# ProProject__CW32__2024-01-23.net
KiCad netlist of a schematic drawn in EasyEDA Pro
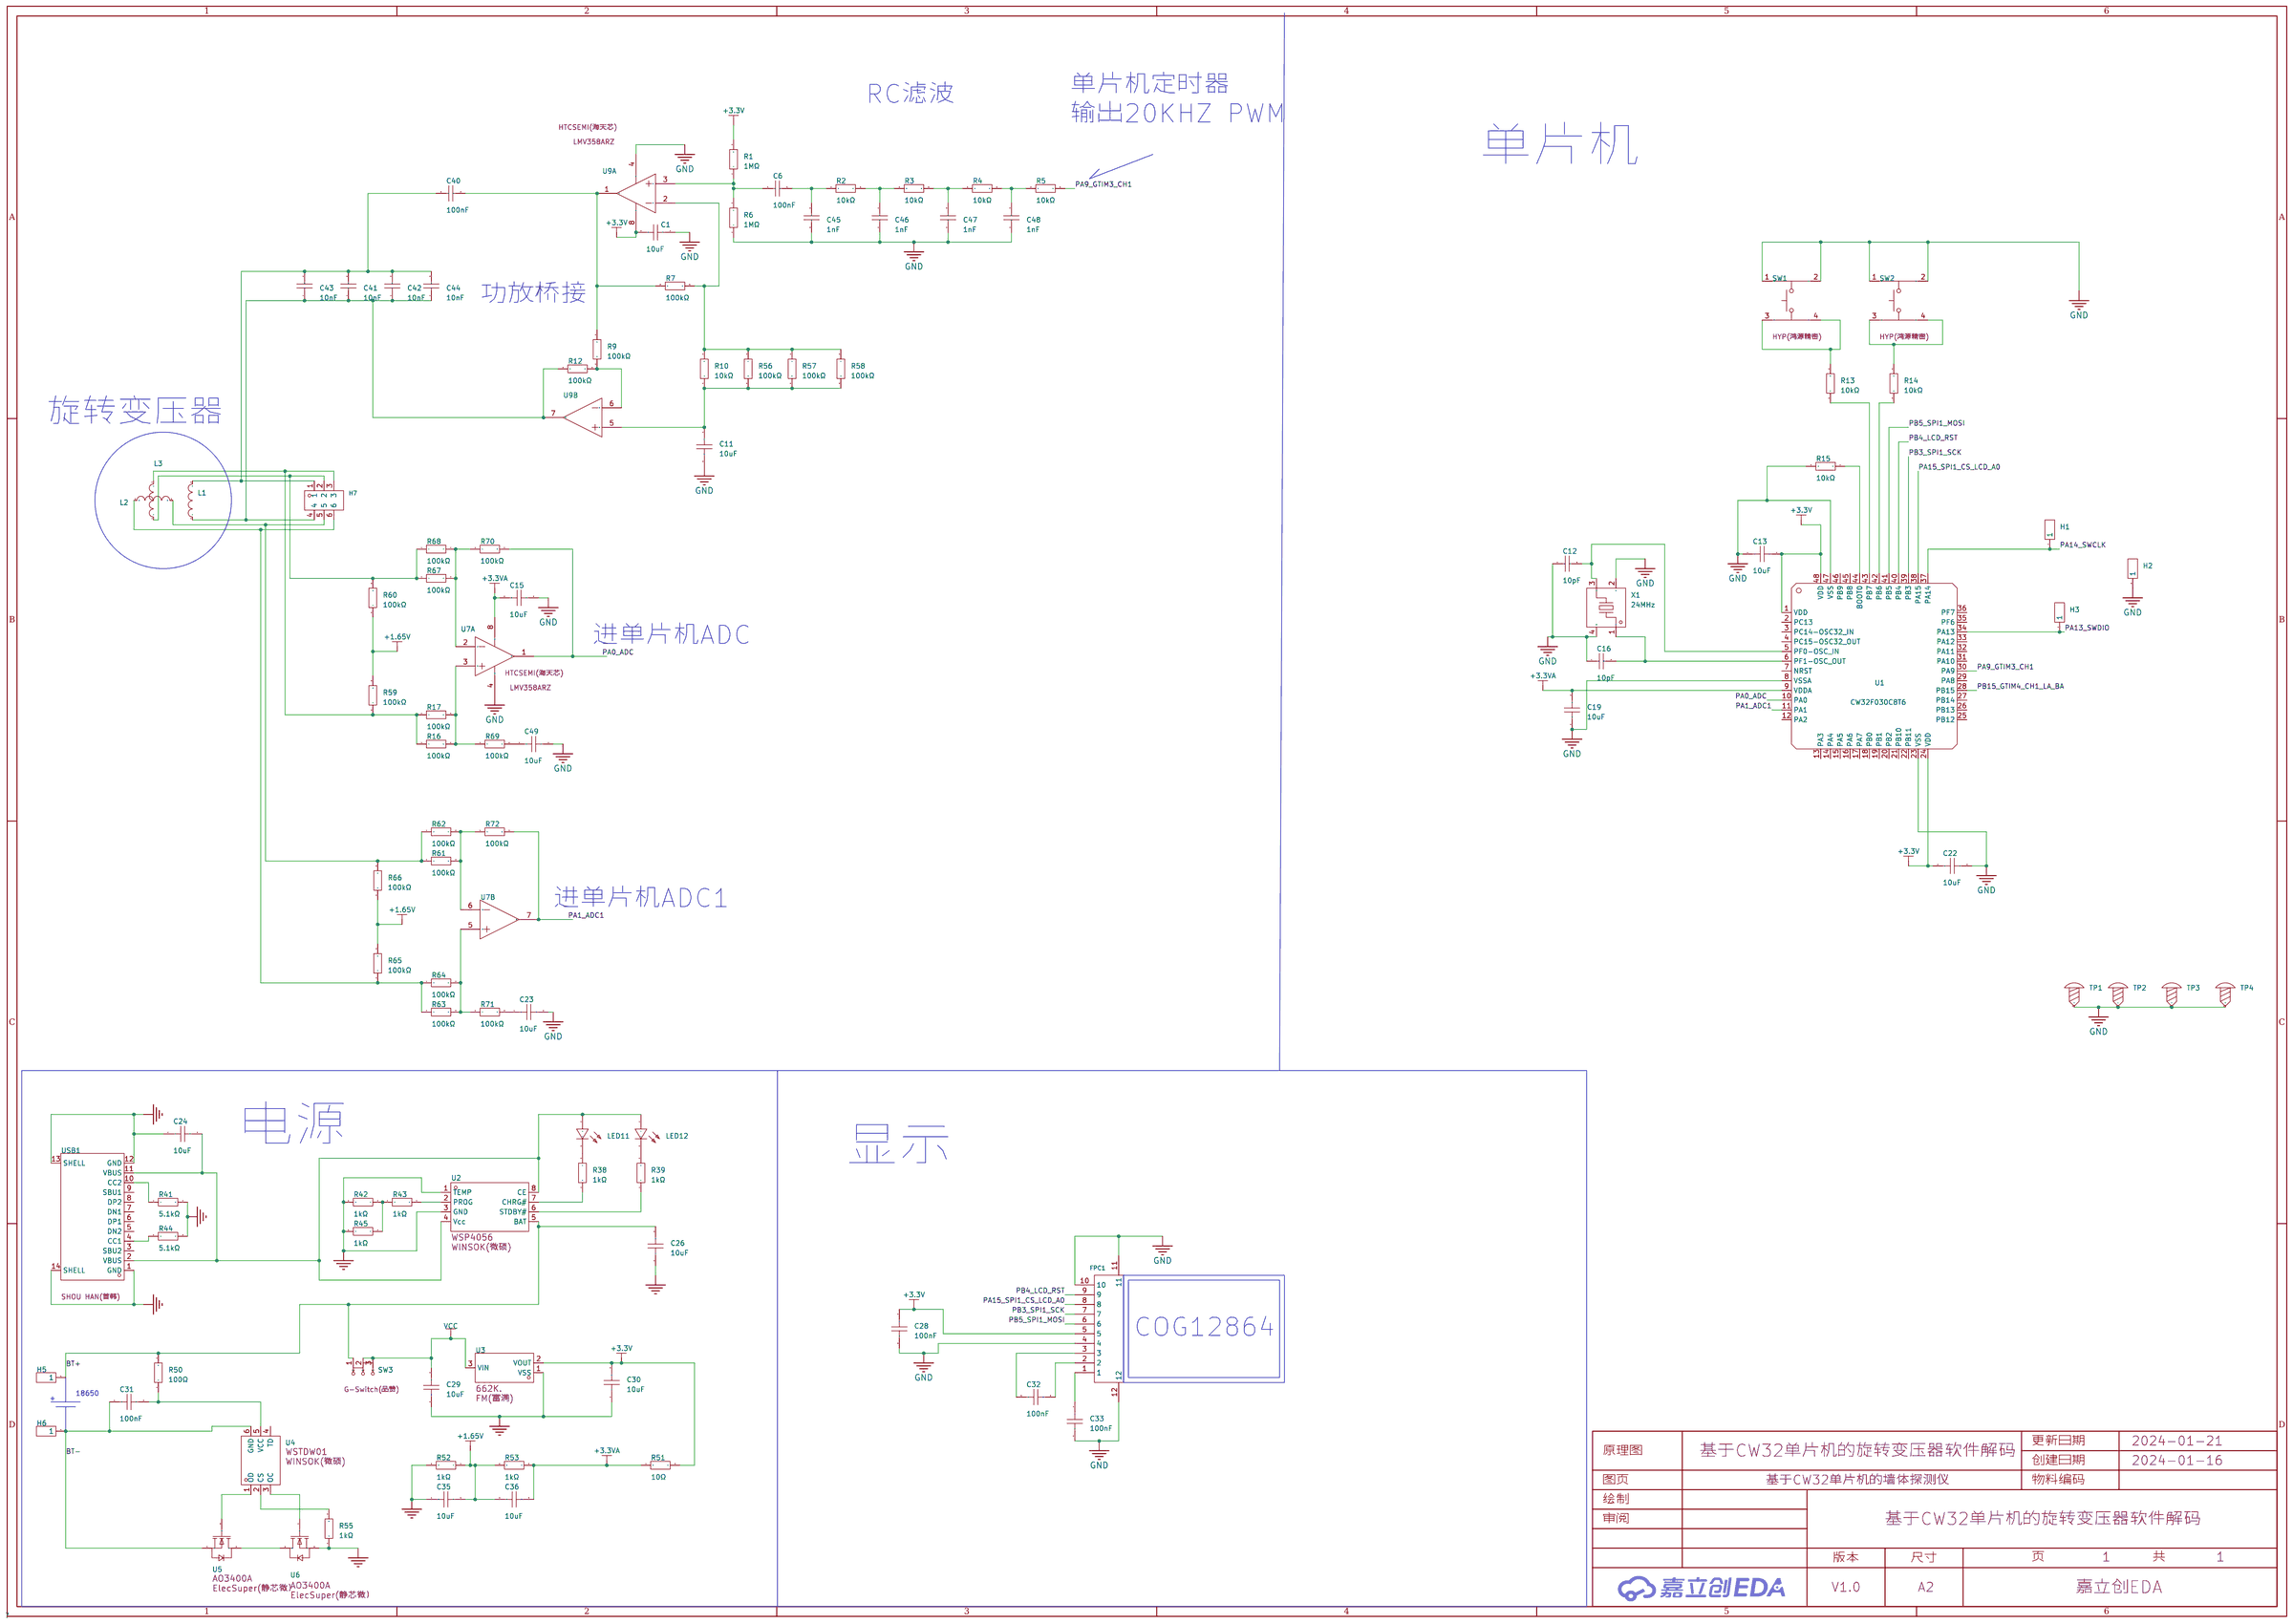
[diagram p0: schematic sheet]

(export (version "E")
  (design (tool "Eeschema 10.0.6"))
  (components
    (comp (ref "C1")
      (value "10uF")
      (footprint "easyedapro:C0603")
      (description "容值:10uF;精度:±10%;额定电压:10V;材质(温度系数):X5R;")
      (fields
        (field (name "Manufacturer Part") "CL10A106KP8NNNC")
        (field (name "Manufacturer") "SAMSUNG(三星)")
      )
      (libsource (lib "easyedapro") (part "CL10A106KP8NNNC"))
    )
    (comp (ref "C6")
      (value "100nF")
      (footprint "easyedapro:C0603")
      (description "容值:100nF;精度:±10%;额定电压:50V;材质(温度系数):X7R;")
      (fields (field (name "Manufacturer Part") "0603B104K500NT") (field (name "Manufacturer") "FH(风华)"))
      (libsource (lib "easyedapro") (part "0603B104K500NT"))
    )
    (comp (ref "C11")
      (value "10uF")
      (footprint "easyedapro:C0603")
      (description "容值:10uF;精度:±10%;额定电压:10V;材质(温度系数):X5R;")
      (fields
        (field (name "Manufacturer Part") "CL10A106KP8NNNC")
        (field (name "Manufacturer") "SAMSUNG(三星)")
      )
      (libsource (lib "easyedapro") (part "CL10A106KP8NNNC"))
    )
    (comp (ref "C12")
      (value "10pF")
      (footprint "easyedapro:C0603")
      (description "容值:10pF;精度:±5%;额定电压:50V;材质(温度系数):NP0;")
      (fields
        (field (name "Manufacturer Part") "CC0603JRNPO9BN100")
        (field (name "Manufacturer") "YAGEO(国巨)")
      )
      (libsource (lib "easyedapro") (part "CC0603JRNPO9BN100"))
    )
    (comp (ref "C13")
      (value "10uF")
      (footprint "easyedapro:C0603")
      (description "容值:10uF;精度:±10%;额定电压:10V;材质(温度系数):X5R;")
      (fields
        (field (name "Manufacturer Part") "CL10A106KP8NNNC")
        (field (name "Manufacturer") "SAMSUNG(三星)")
      )
      (libsource (lib "easyedapro") (part "CL10A106KP8NNNC"))
    )
    (comp (ref "C15")
      (value "10uF")
      (footprint "easyedapro:C0603")
      (description "容值:10uF;精度:±10%;额定电压:10V;材质(温度系数):X5R;")
      (fields
        (field (name "Manufacturer Part") "CL10A106KP8NNNC")
        (field (name "Manufacturer") "SAMSUNG(三星)")
      )
      (libsource (lib "easyedapro") (part "CL10A106KP8NNNC"))
    )
    (comp (ref "C16")
      (value "10pF")
      (footprint "easyedapro:C0603")
      (description "容值:10pF;精度:±5%;额定电压:50V;材质(温度系数):NP0;")
      (fields
        (field (name "Manufacturer Part") "CC0603JRNPO9BN100")
        (field (name "Manufacturer") "YAGEO(国巨)")
      )
      (libsource (lib "easyedapro") (part "CC0603JRNPO9BN100"))
    )
    (comp (ref "C19")
      (value "10uF")
      (footprint "easyedapro:C0603")
      (description "容值:10uF;精度:±10%;额定电压:10V;材质(温度系数):X5R;")
      (fields
        (field (name "Manufacturer Part") "CL10A106KP8NNNC")
        (field (name "Manufacturer") "SAMSUNG(三星)")
      )
      (libsource (lib "easyedapro") (part "CL10A106KP8NNNC"))
    )
    (comp (ref "C22")
      (value "10uF")
      (footprint "easyedapro:C0603")
      (description "容值:10uF;精度:±10%;额定电压:10V;材质(温度系数):X5R;")
      (fields
        (field (name "Manufacturer Part") "CL10A106KP8NNNC")
        (field (name "Manufacturer") "SAMSUNG(三星)")
      )
      (libsource (lib "easyedapro") (part "CL10A106KP8NNNC"))
    )
    (comp (ref "C23")
      (value "10uF")
      (footprint "easyedapro:C0603")
      (description "容值:10uF;精度:±10%;额定电压:10V;材质(温度系数):X5R;")
      (fields
        (field (name "Manufacturer Part") "CL10A106KP8NNNC")
        (field (name "Manufacturer") "SAMSUNG(三星)")
      )
      (libsource (lib "easyedapro") (part "CL10A106KP8NNNC"))
    )
    (comp (ref "C24")
      (value "10uF")
      (footprint "easyedapro:C0603")
      (description "容值:10uF;精度:±10%;额定电压:10V;材质(温度系数):X5R;")
      (fields
        (field (name "Manufacturer Part") "CL10A106KP8NNNC")
        (field (name "Manufacturer") "SAMSUNG(三星)")
      )
      (libsource (lib "easyedapro") (part "CL10A106KP8NNNC"))
    )
    (comp (ref "C26")
      (value "10uF")
      (footprint "easyedapro:C0603")
      (description "容值:10uF;精度:±10%;额定电压:10V;材质(温度系数):X5R;")
      (fields
        (field (name "Manufacturer Part") "CL10A106KP8NNNC")
        (field (name "Manufacturer") "SAMSUNG(三星)")
      )
      (libsource (lib "easyedapro") (part "CL10A106KP8NNNC"))
    )
    (comp (ref "C28")
      (value "100nF")
      (footprint "easyedapro:C0603")
      (description "容值:100nF;精度:±10%;额定电压:50V;材质(温度系数):X7R;")
      (fields
        (field (name "Manufacturer Part") "CC0603KRX7R9BB104")
        (field (name "Manufacturer") "YAGEO(国巨)")
      )
      (libsource (lib "easyedapro") (part "CC0603KRX7R9BB104"))
    )
    (comp (ref "C29")
      (value "10uF")
      (footprint "easyedapro:C0603")
      (description "容值:10uF;精度:±10%;额定电压:10V;材质(温度系数):X5R;")
      (fields
        (field (name "Manufacturer Part") "CL10A106KP8NNNC")
        (field (name "Manufacturer") "SAMSUNG(三星)")
      )
      (libsource (lib "easyedapro") (part "CL10A106KP8NNNC"))
    )
    (comp (ref "C30")
      (value "10uF")
      (footprint "easyedapro:C0603")
      (description "容值:10uF;精度:±10%;额定电压:10V;材质(温度系数):X5R;")
      (fields
        (field (name "Manufacturer Part") "CL10A106KP8NNNC")
        (field (name "Manufacturer") "SAMSUNG(三星)")
      )
      (libsource (lib "easyedapro") (part "CL10A106KP8NNNC"))
    )
    (comp (ref "C31")
      (value "100nF")
      (footprint "easyedapro:C0603")
      (description "容值:100nF;精度:±10%;额定电压:50V;材质(温度系数):X7R;")
      (fields
        (field (name "Manufacturer Part") "CC0603KRX7R9BB104")
        (field (name "Manufacturer") "YAGEO(国巨)")
      )
      (libsource (lib "easyedapro") (part "CC0603KRX7R9BB104"))
    )
    (comp (ref "C32")
      (value "100nF")
      (footprint "easyedapro:C0603")
      (description "容值:100nF;精度:±10%;额定电压:50V;材质(温度系数):X7R;")
      (fields
        (field (name "Manufacturer Part") "CC0603KRX7R9BB104")
        (field (name "Manufacturer") "YAGEO(国巨)")
      )
      (libsource (lib "easyedapro") (part "CC0603KRX7R9BB104"))
    )
    (comp (ref "C33")
      (value "100nF")
      (footprint "easyedapro:C0603")
      (description "容值:100nF;精度:±10%;额定电压:50V;材质(温度系数):X7R;")
      (fields
        (field (name "Manufacturer Part") "CC0603KRX7R9BB104")
        (field (name "Manufacturer") "YAGEO(国巨)")
      )
      (libsource (lib "easyedapro") (part "CC0603KRX7R9BB104"))
    )
    (comp (ref "C35")
      (value "10uF")
      (footprint "easyedapro:C0603")
      (description "容值:10uF;精度:±10%;额定电压:10V;材质(温度系数):X5R;")
      (fields
        (field (name "Manufacturer Part") "CL10A106KP8NNNC")
        (field (name "Manufacturer") "SAMSUNG(三星)")
      )
      (libsource (lib "easyedapro") (part "CL10A106KP8NNNC"))
    )
    (comp (ref "C36")
      (value "10uF")
      (footprint "easyedapro:C0603")
      (description "容值:10uF;精度:±10%;额定电压:10V;材质(温度系数):X5R;")
      (fields
        (field (name "Manufacturer Part") "CL10A106KP8NNNC")
        (field (name "Manufacturer") "SAMSUNG(三星)")
      )
      (libsource (lib "easyedapro") (part "CL10A106KP8NNNC"))
    )
    (comp (ref "C40")
      (value "100nF")
      (footprint "easyedapro:C0603")
      (description "容值:100nF;精度:±10%;额定电压:50V;材质(温度系数):X7R;")
      (fields (field (name "Manufacturer Part") "0603B104K500NT") (field (name "Manufacturer") "FH(风华)"))
      (libsource (lib "easyedapro") (part "0603B104K500NT"))
    )
    (comp (ref "C41")
      (value "10nF")
      (footprint "easyedapro:C0603")
      (description "容值:10nF;精度:±10%;额定电压:50V;材质(温度系数):X7R;")
      (fields
        (field (name "Manufacturer Part") "CC0603KRX7R9BB103")
        (field (name "Manufacturer") "YAGEO(国巨)")
      )
      (libsource (lib "easyedapro") (part "CC0603KRX7R9BB103"))
    )
    (comp (ref "C42")
      (value "10nF")
      (footprint "easyedapro:C0603")
      (description "容值:10nF;精度:±10%;额定电压:50V;材质(温度系数):X7R;")
      (fields
        (field (name "Manufacturer Part") "CC0603KRX7R9BB103")
        (field (name "Manufacturer") "YAGEO(国巨)")
      )
      (libsource (lib "easyedapro") (part "CC0603KRX7R9BB103"))
    )
    (comp (ref "C43")
      (value "10nF")
      (footprint "easyedapro:C0603")
      (description "容值:10nF;精度:±10%;额定电压:50V;材质(温度系数):X7R;")
      (fields
        (field (name "Manufacturer Part") "CC0603KRX7R9BB103")
        (field (name "Manufacturer") "YAGEO(国巨)")
      )
      (libsource (lib "easyedapro") (part "CC0603KRX7R9BB103"))
    )
    (comp (ref "C44")
      (value "10nF")
      (footprint "easyedapro:C0603")
      (description "容值:10nF;精度:±10%;额定电压:50V;材质(温度系数):X7R;")
      (fields
        (field (name "Manufacturer Part") "CC0603KRX7R9BB103")
        (field (name "Manufacturer") "YAGEO(国巨)")
      )
      (libsource (lib "easyedapro") (part "CC0603KRX7R9BB103"))
    )
    (comp (ref "C45")
      (value "1nF")
      (footprint "easyedapro:C0603")
      (description "容值:1nF;精度:±5%;额定电压:50V;材质(温度系数):NP0;")
      (fields
        (field (name "Manufacturer Part") "CC0603JRNPO9BN102")
        (field (name "Manufacturer") "YAGEO(国巨)")
      )
      (libsource (lib "easyedapro") (part "CC0603JRNPO9BN102"))
    )
    (comp (ref "C46")
      (value "1nF")
      (footprint "easyedapro:C0603")
      (description "容值:1nF;精度:±5%;额定电压:50V;材质(温度系数):NP0;")
      (fields
        (field (name "Manufacturer Part") "CC0603JRNPO9BN102")
        (field (name "Manufacturer") "YAGEO(国巨)")
      )
      (libsource (lib "easyedapro") (part "CC0603JRNPO9BN102"))
    )
    (comp (ref "C47")
      (value "1nF")
      (footprint "easyedapro:C0603")
      (description "容值:1nF;精度:±5%;额定电压:50V;材质(温度系数):NP0;")
      (fields
        (field (name "Manufacturer Part") "CC0603JRNPO9BN102")
        (field (name "Manufacturer") "YAGEO(国巨)")
      )
      (libsource (lib "easyedapro") (part "CC0603JRNPO9BN102"))
    )
    (comp (ref "C48")
      (value "1nF")
      (footprint "easyedapro:C0603")
      (description "容值:1nF;精度:±5%;额定电压:50V;材质(温度系数):NP0;")
      (fields
        (field (name "Manufacturer Part") "CC0603JRNPO9BN102")
        (field (name "Manufacturer") "YAGEO(国巨)")
      )
      (libsource (lib "easyedapro") (part "CC0603JRNPO9BN102"))
    )
    (comp (ref "C49")
      (value "10uF")
      (footprint "easyedapro:C0603")
      (description "容值:10uF;精度:±10%;额定电压:10V;材质(温度系数):X5R;")
      (fields
        (field (name "Manufacturer Part") "CL10A106KP8NNNC")
        (field (name "Manufacturer") "SAMSUNG(三星)")
      )
      (libsource (lib "easyedapro") (part "CL10A106KP8NNNC"))
    )
    (comp (ref "FPC1")
      (value "{ManufacturerPart!}")
      (footprint "easyedapro:FPC-SMD_10P-P1.0_FGS-XJ-H2.0")
      (description "间距:1mm;触点数量:10;锁定特性:翻盖式;安装类型:卧贴;触点类型:下接;")
      (fields (field (name "Manufacturer Part") "AFA01-S10FCA-00") (field (name "Manufacturer") "JS(钜硕电子)"))
      (libsource (lib "easyedapro") (part "AFA01-S10FCA-00"))
    )
    (comp (ref "H1")
      (value "~")
      (footprint "easyedapro:HDR-TH_1P-V-M_XKB_X4611WV-01I-C28D40")
      (libsource (lib "easyedapro") (part "HDR_1x1"))
    )
    (comp (ref "H2")
      (value "~")
      (footprint "easyedapro:HDR-TH_1P-V-M_XKB_X4611WV-01I-C28D40")
      (libsource (lib "easyedapro") (part "HDR_1x1"))
    )
    (comp (ref "H3")
      (value "~")
      (footprint "easyedapro:HDR-TH_1P-V-M_XKB_X4611WV-01I-C28D40")
      (libsource (lib "easyedapro") (part "HDR_1x1"))
    )
    (comp (ref "H5")
      (value "~")
      (footprint "easyedapro:HDR-TH_1P-V-M_XKB_X4611WV-01I-C28D40")
      (libsource (lib "easyedapro") (part "HDR_1x1"))
    )
    (comp (ref "H6")
      (value "~")
      (footprint "easyedapro:HDR-TH_1P-V-M_XKB_X4611WV-01I-C28D40")
      (libsource (lib "easyedapro") (part "HDR_1x1"))
    )
    (comp (ref "H7")
      (value "PZ254-2-03-Z-8.5")
      (footprint "easyedapro:HDR-TH_6P-P2.54-V-M-R2-C3-S2.54")
      (fields (field (name "Manufacturer") "HCTL(华灿天禄)"))
      (libsource (lib "easyedapro") (part "PZ254-2-03-Z-8.5"))
    )
    (comp (ref "L1")
      (value "6.3uH")
      (footprint "easyedapro:L1206")
      (libsource (lib "easyedapro") (part "CMI321609VR27KT"))
    )
    (comp (ref "L2")
      (value "10uH")
      (footprint "easyedapro:L1206")
      (libsource (lib "easyedapro") (part "CMI321609VR27KT"))
    )
    (comp (ref "L3")
      (value "10uH")
      (footprint "easyedapro:L1206")
      (libsource (lib "easyedapro") (part "CMI321609VR27KT"))
    )
    (comp (ref "LED11")
      (value "204-10SURD/S530-A3-L")
      (footprint "easyedapro:LED-TH_BD3.0-P2.54-FD")
      (description "发光颜色:红灯;二极管配置:-;主波长:624nm;色温:-;功率:60mW;安装方式:-;")
      (fields (field (name "Manufacturer") "EVERLIGHT(亿光)"))
      (libsource (lib "easyedapro") (part "204-10SURD/S530-A3-L"))
    )
    (comp (ref "LED12")
      (value "204-10SURD/S530-A3-L")
      (footprint "easyedapro:LED-TH_BD3.0-P2.54-FD")
      (description "发光颜色:红灯;二极管配置:-;主波长:624nm;色温:-;功率:60mW;安装方式:-;")
      (fields (field (name "Manufacturer") "EVERLIGHT(亿光)"))
      (libsource (lib "easyedapro") (part "204-10SURD/S530-A3-L"))
    )
    (comp (ref "R1")
      (value "1MΩ")
      (footprint "easyedapro:R0603")
      (description "电阻类型:厚膜电阻;阻值:1MΩ;精度:±1%;功率:100mW;")
      (fields
        (field (name "Manufacturer Part") "0603WAF1004T5E")
        (field (name "Manufacturer") "UNI-ROYAL(厚声)")
      )
      (libsource (lib "easyedapro") (part "0603WAF1004T5E"))
    )
    (comp (ref "R2")
      (value "10kΩ")
      (footprint "easyedapro:R0603")
      (description "电阻类型:厚膜电阻;阻值:10kΩ;精度:±1%;功率:100mW;")
      (fields (field (name "Manufacturer Part") "RC0603FR-0710KL") (field (name "Manufacturer") "YAGEO(国巨)"))
      (libsource (lib "easyedapro") (part "RC0603FR-0710KL"))
    )
    (comp (ref "R3")
      (value "10kΩ")
      (footprint "easyedapro:R0603")
      (description "电阻类型:厚膜电阻;阻值:10kΩ;精度:±1%;功率:100mW;")
      (fields (field (name "Manufacturer Part") "RC0603FR-0710KL") (field (name "Manufacturer") "YAGEO(国巨)"))
      (libsource (lib "easyedapro") (part "RC0603FR-0710KL"))
    )
    (comp (ref "R4")
      (value "10kΩ")
      (footprint "easyedapro:R0603")
      (description "电阻类型:厚膜电阻;阻值:10kΩ;精度:±1%;功率:100mW;")
      (fields (field (name "Manufacturer Part") "RC0603FR-0710KL") (field (name "Manufacturer") "YAGEO(国巨)"))
      (libsource (lib "easyedapro") (part "RC0603FR-0710KL"))
    )
    (comp (ref "R5")
      (value "10kΩ")
      (footprint "easyedapro:R0603")
      (description "电阻类型:厚膜电阻;阻值:10kΩ;精度:±1%;功率:100mW;")
      (fields (field (name "Manufacturer Part") "RC0603FR-0710KL") (field (name "Manufacturer") "YAGEO(国巨)"))
      (libsource (lib "easyedapro") (part "RC0603FR-0710KL"))
    )
    (comp (ref "R6")
      (value "1MΩ")
      (footprint "easyedapro:R0603")
      (description "电阻类型:厚膜电阻;阻值:1MΩ;精度:±1%;功率:100mW;")
      (fields
        (field (name "Manufacturer Part") "0603WAF1004T5E")
        (field (name "Manufacturer") "UNI-ROYAL(厚声)")
      )
      (libsource (lib "easyedapro") (part "0603WAF1004T5E"))
    )
    (comp (ref "R7")
      (value "100kΩ")
      (footprint "easyedapro:R0603")
      (description "电阻类型:厚膜电阻;阻值:100kΩ;精度:±1%;功率:100mW;")
      (fields (field (name "Manufacturer Part") "RC0603FR-07100KL") (field (name "Manufacturer") "YAGEO(国巨)"))
      (libsource (lib "easyedapro") (part "RC0603FR-07100KL"))
    )
    (comp (ref "R9")
      (value "100kΩ")
      (footprint "easyedapro:R0603")
      (description "电阻类型:厚膜电阻;阻值:100kΩ;精度:±1%;功率:100mW;")
      (fields (field (name "Manufacturer Part") "RC0603FR-07100KL") (field (name "Manufacturer") "YAGEO(国巨)"))
      (libsource (lib "easyedapro") (part "RC0603FR-07100KL"))
    )
    (comp (ref "R10")
      (value "10kΩ")
      (footprint "easyedapro:R0603")
      (description "电阻类型:厚膜电阻;阻值:10kΩ;精度:±1%;功率:100mW;")
      (fields (field (name "Manufacturer Part") "RC0603FR-0710KL") (field (name "Manufacturer") "YAGEO(国巨)"))
      (libsource (lib "easyedapro") (part "RC0603FR-0710KL"))
    )
    (comp (ref "R12")
      (value "100kΩ")
      (footprint "easyedapro:R0603")
      (description "电阻类型:厚膜电阻;阻值:100kΩ;精度:±1%;功率:100mW;")
      (fields (field (name "Manufacturer Part") "RC0603FR-07100KL") (field (name "Manufacturer") "YAGEO(国巨)"))
      (libsource (lib "easyedapro") (part "RC0603FR-07100KL"))
    )
    (comp (ref "R13")
      (value "10kΩ")
      (footprint "easyedapro:R0603")
      (description "电阻类型:厚膜电阻;阻值:10kΩ;精度:±1%;功率:100mW;")
      (fields (field (name "Manufacturer Part") "RC0603FR-0710KL") (field (name "Manufacturer") "YAGEO(国巨)"))
      (libsource (lib "easyedapro") (part "RC0603FR-0710KL"))
    )
    (comp (ref "R14")
      (value "10kΩ")
      (footprint "easyedapro:R0603")
      (description "电阻类型:厚膜电阻;阻值:10kΩ;精度:±1%;功率:100mW;")
      (fields (field (name "Manufacturer Part") "RC0603FR-0710KL") (field (name "Manufacturer") "YAGEO(国巨)"))
      (libsource (lib "easyedapro") (part "RC0603FR-0710KL"))
    )
    (comp (ref "R15")
      (value "10kΩ")
      (footprint "easyedapro:R0603")
      (description "电阻类型:厚膜电阻;阻值:10kΩ;精度:±1%;功率:100mW;")
      (fields (field (name "Manufacturer Part") "RC0603FR-0710KL") (field (name "Manufacturer") "YAGEO(国巨)"))
      (libsource (lib "easyedapro") (part "RC0603FR-0710KL"))
    )
    (comp (ref "R16")
      (value "100kΩ")
      (footprint "easyedapro:R0603")
      (description "电阻类型:厚膜电阻;阻值:100kΩ;精度:±1%;功率:100mW;")
      (fields (field (name "Manufacturer Part") "RC0603FR-07100KL") (field (name "Manufacturer") "YAGEO(国巨)"))
      (libsource (lib "easyedapro") (part "RC0603FR-07100KL"))
    )
    (comp (ref "R17")
      (value "100kΩ")
      (footprint "easyedapro:R0603")
      (description "电阻类型:厚膜电阻;阻值:100kΩ;精度:±1%;功率:100mW;")
      (fields (field (name "Manufacturer Part") "RC0603FR-07100KL") (field (name "Manufacturer") "YAGEO(国巨)"))
      (libsource (lib "easyedapro") (part "RC0603FR-07100KL"))
    )
    (comp (ref "R38")
      (value "1kΩ")
      (footprint "easyedapro:R0603")
      (description "电阻类型:厚膜电阻;阻值:1kΩ;精度:±1%;功率:100mW;")
      (fields (field (name "Manufacturer Part") "RC0603FR-071KL") (field (name "Manufacturer") "YAGEO(国巨)"))
      (libsource (lib "easyedapro") (part "RC0603FR-071KL"))
    )
    (comp (ref "R39")
      (value "1kΩ")
      (footprint "easyedapro:R0603")
      (description "电阻类型:厚膜电阻;阻值:1kΩ;精度:±1%;功率:100mW;")
      (fields (field (name "Manufacturer Part") "RC0603FR-071KL") (field (name "Manufacturer") "YAGEO(国巨)"))
      (libsource (lib "easyedapro") (part "RC0603FR-071KL"))
    )
    (comp (ref "R41")
      (value "5.1kΩ")
      (footprint "easyedapro:R0603")
      (description "电阻类型:厚膜电阻;阻值:10kΩ;精度:±1%;功率:100mW;")
      (fields (field (name "Manufacturer Part") "RC0603FR-0710KL") (field (name "Manufacturer") "YAGEO(国巨)"))
      (libsource (lib "easyedapro") (part "RC0603FR-0710KL"))
    )
    (comp (ref "R42")
      (value "1kΩ")
      (footprint "easyedapro:R0603")
      (description "电阻类型:厚膜电阻;阻值:1kΩ;精度:±1%;功率:100mW;")
      (fields (field (name "Manufacturer Part") "RC0603FR-071KL") (field (name "Manufacturer") "YAGEO(国巨)"))
      (libsource (lib "easyedapro") (part "RC0603FR-071KL"))
    )
    (comp (ref "R43")
      (value "1kΩ")
      (footprint "easyedapro:R0603")
      (description "电阻类型:厚膜电阻;阻值:1kΩ;精度:±1%;功率:100mW;")
      (fields (field (name "Manufacturer Part") "RC0603FR-071KL") (field (name "Manufacturer") "YAGEO(国巨)"))
      (libsource (lib "easyedapro") (part "RC0603FR-071KL"))
    )
    (comp (ref "R44")
      (value "5.1kΩ")
      (footprint "easyedapro:R0603")
      (description "电阻类型:厚膜电阻;阻值:10kΩ;精度:±1%;功率:100mW;")
      (fields (field (name "Manufacturer Part") "RC0603FR-0710KL") (field (name "Manufacturer") "YAGEO(国巨)"))
      (libsource (lib "easyedapro") (part "RC0603FR-0710KL"))
    )
    (comp (ref "R45")
      (value "1kΩ")
      (footprint "easyedapro:R0603")
      (description "电阻类型:厚膜电阻;阻值:1kΩ;精度:±1%;功率:100mW;")
      (fields (field (name "Manufacturer Part") "RC0603FR-071KL") (field (name "Manufacturer") "YAGEO(国巨)"))
      (libsource (lib "easyedapro") (part "RC0603FR-071KL"))
    )
    (comp (ref "R50")
      (value "100Ω")
      (footprint "easyedapro:R0603")
      (description "电阻类型:厚膜电阻;阻值:100Ω;精度:±1%;功率:100mW;")
      (fields (field (name "Manufacturer Part") "RC0603FR-07100RL") (field (name "Manufacturer") "YAGEO(国巨)"))
      (libsource (lib "easyedapro") (part "RC0603FR-07100RL"))
    )
    (comp (ref "R51")
      (value "10Ω")
      (footprint "easyedapro:R0603")
      (description "电阻类型:厚膜电阻;阻值:10Ω;精度:±1%;功率:100mW;")
      (fields
        (field (name "Manufacturer Part") "0603WAF100JT5E")
        (field (name "Manufacturer") "UNI-ROYAL(厚声)")
      )
      (libsource (lib "easyedapro") (part "0603WAF100JT5E"))
    )
    (comp (ref "R52")
      (value "1kΩ")
      (footprint "easyedapro:R0603")
      (description "电阻类型:厚膜电阻;阻值:1kΩ;精度:±1%;功率:100mW;")
      (fields (field (name "Manufacturer Part") "RC0603FR-071KL") (field (name "Manufacturer") "YAGEO(国巨)"))
      (libsource (lib "easyedapro") (part "RC0603FR-071KL"))
    )
    (comp (ref "R53")
      (value "1kΩ")
      (footprint "easyedapro:R0603")
      (description "电阻类型:厚膜电阻;阻值:1kΩ;精度:±1%;功率:100mW;")
      (fields (field (name "Manufacturer Part") "RC0603FR-071KL") (field (name "Manufacturer") "YAGEO(国巨)"))
      (libsource (lib "easyedapro") (part "RC0603FR-071KL"))
    )
    (comp (ref "R55")
      (value "1kΩ")
      (footprint "easyedapro:R0603")
      (description "电阻类型:厚膜电阻;阻值:1kΩ;精度:±1%;功率:100mW;")
      (fields (field (name "Manufacturer Part") "RC0603FR-071KL") (field (name "Manufacturer") "YAGEO(国巨)"))
      (libsource (lib "easyedapro") (part "RC0603FR-071KL"))
    )
    (comp (ref "R56")
      (value "100kΩ")
      (footprint "easyedapro:R0603")
      (description "电阻类型:厚膜电阻;阻值:100kΩ;精度:±1%;功率:100mW;")
      (fields (field (name "Manufacturer Part") "RC0603FR-07100KL") (field (name "Manufacturer") "YAGEO(国巨)"))
      (libsource (lib "easyedapro") (part "RC0603FR-07100KL"))
    )
    (comp (ref "R57")
      (value "100kΩ")
      (footprint "easyedapro:R0603")
      (description "电阻类型:厚膜电阻;阻值:100kΩ;精度:±1%;功率:100mW;")
      (fields (field (name "Manufacturer Part") "RC0603FR-07100KL") (field (name "Manufacturer") "YAGEO(国巨)"))
      (libsource (lib "easyedapro") (part "RC0603FR-07100KL"))
    )
    (comp (ref "R58")
      (value "100kΩ")
      (footprint "easyedapro:R0603")
      (description "电阻类型:厚膜电阻;阻值:100kΩ;精度:±1%;功率:100mW;")
      (fields (field (name "Manufacturer Part") "RC0603FR-07100KL") (field (name "Manufacturer") "YAGEO(国巨)"))
      (libsource (lib "easyedapro") (part "RC0603FR-07100KL"))
    )
    (comp (ref "R59")
      (value "100kΩ")
      (footprint "easyedapro:R0603")
      (description "电阻类型:厚膜电阻;阻值:100kΩ;精度:±1%;功率:100mW;")
      (fields (field (name "Manufacturer Part") "RC0603FR-07100KL") (field (name "Manufacturer") "YAGEO(国巨)"))
      (libsource (lib "easyedapro") (part "RC0603FR-07100KL"))
    )
    (comp (ref "R60")
      (value "100kΩ")
      (footprint "easyedapro:R0603")
      (description "电阻类型:厚膜电阻;阻值:100kΩ;精度:±1%;功率:100mW;")
      (fields (field (name "Manufacturer Part") "RC0603FR-07100KL") (field (name "Manufacturer") "YAGEO(国巨)"))
      (libsource (lib "easyedapro") (part "RC0603FR-07100KL"))
    )
    (comp (ref "R61")
      (value "100kΩ")
      (footprint "easyedapro:R0603")
      (description "电阻类型:厚膜电阻;阻值:100kΩ;精度:±1%;功率:100mW;")
      (fields (field (name "Manufacturer Part") "RC0603FR-07100KL") (field (name "Manufacturer") "YAGEO(国巨)"))
      (libsource (lib "easyedapro") (part "RC0603FR-07100KL"))
    )
    (comp (ref "R62")
      (value "100kΩ")
      (footprint "easyedapro:R0603")
      (description "电阻类型:厚膜电阻;阻值:100kΩ;精度:±1%;功率:100mW;")
      (fields (field (name "Manufacturer Part") "RC0603FR-07100KL") (field (name "Manufacturer") "YAGEO(国巨)"))
      (libsource (lib "easyedapro") (part "RC0603FR-07100KL"))
    )
    (comp (ref "R63")
      (value "100kΩ")
      (footprint "easyedapro:R0603")
      (description "电阻类型:厚膜电阻;阻值:100kΩ;精度:±1%;功率:100mW;")
      (fields (field (name "Manufacturer Part") "RC0603FR-07100KL") (field (name "Manufacturer") "YAGEO(国巨)"))
      (libsource (lib "easyedapro") (part "RC0603FR-07100KL"))
    )
    (comp (ref "R64")
      (value "100kΩ")
      (footprint "easyedapro:R0603")
      (description "电阻类型:厚膜电阻;阻值:100kΩ;精度:±1%;功率:100mW;")
      (fields (field (name "Manufacturer Part") "RC0603FR-07100KL") (field (name "Manufacturer") "YAGEO(国巨)"))
      (libsource (lib "easyedapro") (part "RC0603FR-07100KL"))
    )
    (comp (ref "R65")
      (value "100kΩ")
      (footprint "easyedapro:R0603")
      (description "电阻类型:厚膜电阻;阻值:100kΩ;精度:±1%;功率:100mW;")
      (fields (field (name "Manufacturer Part") "RC0603FR-07100KL") (field (name "Manufacturer") "YAGEO(国巨)"))
      (libsource (lib "easyedapro") (part "RC0603FR-07100KL"))
    )
    (comp (ref "R66")
      (value "100kΩ")
      (footprint "easyedapro:R0603")
      (description "电阻类型:厚膜电阻;阻值:100kΩ;精度:±1%;功率:100mW;")
      (fields (field (name "Manufacturer Part") "RC0603FR-07100KL") (field (name "Manufacturer") "YAGEO(国巨)"))
      (libsource (lib "easyedapro") (part "RC0603FR-07100KL"))
    )
    (comp (ref "R67")
      (value "100kΩ")
      (footprint "easyedapro:R0603")
      (description "电阻类型:厚膜电阻;阻值:100kΩ;精度:±1%;功率:100mW;")
      (fields (field (name "Manufacturer Part") "RC0603FR-07100KL") (field (name "Manufacturer") "YAGEO(国巨)"))
      (libsource (lib "easyedapro") (part "RC0603FR-07100KL"))
    )
    (comp (ref "R68")
      (value "100kΩ")
      (footprint "easyedapro:R0603")
      (description "电阻类型:厚膜电阻;阻值:100kΩ;精度:±1%;功率:100mW;")
      (fields (field (name "Manufacturer Part") "RC0603FR-07100KL") (field (name "Manufacturer") "YAGEO(国巨)"))
      (libsource (lib "easyedapro") (part "RC0603FR-07100KL"))
    )
    (comp (ref "R69")
      (value "100kΩ")
      (footprint "easyedapro:R0603")
      (description "电阻类型:厚膜电阻;阻值:100kΩ;精度:±1%;功率:100mW;")
      (fields (field (name "Manufacturer Part") "RC0603FR-07100KL") (field (name "Manufacturer") "YAGEO(国巨)"))
      (libsource (lib "easyedapro") (part "RC0603FR-07100KL"))
    )
    (comp (ref "R70")
      (value "100kΩ")
      (footprint "easyedapro:R0603")
      (description "电阻类型:厚膜电阻;阻值:100kΩ;精度:±1%;功率:100mW;")
      (fields (field (name "Manufacturer Part") "RC0603FR-07100KL") (field (name "Manufacturer") "YAGEO(国巨)"))
      (libsource (lib "easyedapro") (part "RC0603FR-07100KL"))
    )
    (comp (ref "R71")
      (value "100kΩ")
      (footprint "easyedapro:R0603")
      (description "电阻类型:厚膜电阻;阻值:100kΩ;精度:±1%;功率:100mW;")
      (fields (field (name "Manufacturer Part") "RC0603FR-07100KL") (field (name "Manufacturer") "YAGEO(国巨)"))
      (libsource (lib "easyedapro") (part "RC0603FR-07100KL"))
    )
    (comp (ref "R72")
      (value "100kΩ")
      (footprint "easyedapro:R0603")
      (description "电阻类型:厚膜电阻;阻值:100kΩ;精度:±1%;功率:100mW;")
      (fields (field (name "Manufacturer Part") "RC0603FR-07100KL") (field (name "Manufacturer") "YAGEO(国巨)"))
      (libsource (lib "easyedapro") (part "RC0603FR-07100KL"))
    )
    (comp (ref "SW1")
      (value "{ManufacturerPart!}")
      (footprint "easyedapro:SW-TH_4P-L6.0-W6.0-P3.90-LS6.5")
      (description "触点电流:50mA;额定电压(DC):12V;额定功率:0.6W;绝缘电阻:100MΩ;电路结构:单刀单掷;安装方式:直插;带灯:无;作用力:250gf@±50gf;机械寿命:7万次;带支架:否;")
      (fields
        (field (name "Manufacturer Part") "1TS005A-2500-5001")
        (field (name "Manufacturer") "HYP(鸿源精密)")
      )
      (libsource (lib "easyedapro") (part "1TS005A-2500-5001"))
    )
    (comp (ref "SW2")
      (value "{ManufacturerPart!}")
      (footprint "easyedapro:SW-TH_4P-L6.0-W6.0-P3.90-LS6.5")
      (description "触点电流:50mA;额定电压(DC):12V;额定功率:0.6W;绝缘电阻:100MΩ;电路结构:单刀单掷;安装方式:直插;带灯:无;作用力:250gf@±50gf;机械寿命:7万次;带支架:否;")
      (fields
        (field (name "Manufacturer Part") "1TS005A-2500-5001")
        (field (name "Manufacturer") "HYP(鸿源精密)")
      )
      (libsource (lib "easyedapro") (part "1TS005A-2500-5001"))
    )
    (comp (ref "SW3")
      (value "SS-12F20-G070")
      (footprint "easyedapro:SW-TH_G-SWITCH_SS-12F20-G070")
      (description "额定电流(DC):500mA;额定电压(DC):250V;电路结构:单刀双掷;安装方式:直插;机械寿命:-;开关颜色:黑色;")
      (fields (field (name "Manufacturer") "G-Switch(品赞)"))
      (libsource (lib "easyedapro") (part "SS-12F20-G070"))
    )
    (comp (ref "TP1") (value "~") (footprint "easyedapro:M3螺丝") (libsource (lib "easyedapro") (part "螺丝孔")))
    (comp (ref "TP2") (value "~") (footprint "easyedapro:M3螺丝") (libsource (lib "easyedapro") (part "螺丝孔")))
    (comp (ref "TP3") (value "~") (footprint "easyedapro:M3螺丝") (libsource (lib "easyedapro") (part "螺丝孔")))
    (comp (ref "TP4") (value "~") (footprint "easyedapro:M3螺丝") (libsource (lib "easyedapro") (part "螺丝孔")))
    (comp (ref "U1")
      (value "CW32F030C8T6")
      (footprint "easyedapro:LQFP-48_L7.0-W7.0-P0.50-LS9.0-TL")
      (fields (field (name "Manufacturer") "CW(芯源)"))
      (libsource (lib "easyedapro") (part "CW32F030C8T6_C3019113"))
    )
    (comp (ref "U2")
      (value "WSP4056")
      (footprint "easyedapro:SOP-8_L5.1-W3.9-P1.27-LS6.0-BL")
      (fields (field (name "Manufacturer Part") "WSP4056") (field (name "Manufacturer") "WINSOK(微硕)"))
      (libsource (lib "easyedapro") (part "WSP4056"))
    )
    (comp (ref "U3")
      (value "662K.")
      (footprint "easyedapro:SOT-23-3_L2.9-W1.3-P1.90-LS2.4-BR")
      (description "输出类型:-;")
      (fields (field (name "Manufacturer Part") "662K.") (field (name "Manufacturer") "FM(富满)"))
      (libsource (lib "easyedapro") (part "662K."))
    )
    (comp (ref "U4")
      (value "WSTDW01")
      (footprint "easyedapro:SOT-23-6_L2.9-W1.6-P0.95-LS2.8-BR")
      (description "充电电池的类型:-;电池单元组数:-;最大充电电流:-;充满的电池组电压:-;最大供应电压:-;")
      (fields (field (name "Manufacturer Part") "WSTDW01") (field (name "Manufacturer") "WINSOK(微硕)"))
      (libsource (lib "easyedapro") (part "WSTDW01"))
    )
    (comp (ref "U5")
      (value "AO3400A")
      (footprint "easyedapro:SOT-23-3_L3.0-W1.6-P1.90-LS2.8-BR")
      (description "类型:N沟道;漏源电压(Vdss):30V;连续漏极电流(Id):6A;功率(Pd):1.4W;导通电阻(RDS(on)@Vgs,Id):19mΩ@10V,6.0A;")
      (fields (field (name "Manufacturer Part") "AO3400A") (field (name "Manufacturer") "ElecSuper(静芯微）"))
      (libsource (lib "easyedapro") (part "AO3400A_C5224194"))
    )
    (comp (ref "U6")
      (value "AO3400A")
      (footprint "easyedapro:SOT-23-3_L3.0-W1.6-P1.90-LS2.8-BR")
      (description "类型:N沟道;漏源电压(Vdss):30V;连续漏极电流(Id):6A;功率(Pd):1.4W;导通电阻(RDS(on)@Vgs,Id):19mΩ@10V,6.0A;")
      (fields (field (name "Manufacturer Part") "AO3400A") (field (name "Manufacturer") "ElecSuper(静芯微）"))
      (libsource (lib "easyedapro") (part "AO3400A_C5224194"))
    )
    (comp (ref "U7")
      (value "{ManufacturerPart!}")
      (footprint "easyedapro:SOP-8_L4.9-W3.9-P1.27-LS6.0-BL")
      (description "CMOS低功耗双路运算放大器")
      (fields (field (name "Manufacturer Part") "LMV358ARZ") (field (name "Manufacturer") "HTCSEMI(海天芯)"))
      (libsource (lib "easyedapro") (part "LMV358ARZ"))
    )
    (comp (ref "U9")
      (value "{ManufacturerPart!}")
      (footprint "easyedapro:SOP-8_L4.9-W3.9-P1.27-LS6.0-BL")
      (description "CMOS低功耗双路运算放大器")
      (fields (field (name "Manufacturer Part") "LMV358ARZ") (field (name "Manufacturer") "HTCSEMI(海天芯)"))
      (libsource (lib "easyedapro") (part "LMV358ARZ"))
    )
    (comp (ref "USB1")
      (value "TYPE-C16PIN2MD(073)")
      (footprint "easyedapro:USB-C-SMD_TYPE-C-6PIN-2MD-073")
      (description "连接器类型:Type-C;标准:-;公母:母座;触点数量:16;端口数量:1;安装方式:卧贴;额定电流 - 电源:5A;工作温度范围:-25°C~+85°C;")
      (fields (field (name "Manufacturer") "SHOU HAN(首韩)"))
      (libsource (lib "easyedapro") (part "TYPE-C 16PIN 2MD(073)"))
    )
    (comp (ref "X1")
      (value "24MHz")
      (footprint "easyedapro:CRYSTAL-SMD_4P-L3.2-W2.5-BL")
      (description "频率:24MHz;频率公差:±10ppm;负载电容:9pF;")
      (fields (field (name "Manufacturer Part") "3TJ424000HYFBC") (field (name "Manufacturer") "JYJE(晶友嘉)"))
      (libsource (lib "easyedapro") (part "3TJ424000HYFBC"))
    )
  )
  (nets
    (net (code "1") (name "+1.65V") (class "Default")
      (node (ref "C35") (pin "2") (pinfunction "2_2") (pintype "unspecified"))
      (node (ref "C36") (pin "1") (pinfunction "1_1") (pintype "unspecified"))
      (node (ref "R52") (pin "1") (pinfunction "1_1") (pintype "input"))
      (node (ref "R53") (pin "2") (pinfunction "2_2") (pintype "input"))
      (node (ref "R59") (pin "2") (pinfunction "2_2") (pintype "unspecified"))
      (node (ref "R60") (pin "1") (pinfunction "1_1") (pintype "unspecified"))
      (node (ref "R65") (pin "2") (pinfunction "2_2") (pintype "unspecified"))
      (node (ref "R66") (pin "1") (pinfunction "1_1") (pintype "unspecified"))
    )
    (net (code "2") (name "+3.3V") (class "Default")
      (node (ref "C1") (pin "2") (pinfunction "2_2") (pintype "unspecified"))
      (node (ref "C13") (pin "2") (pinfunction "2_2") (pintype "unspecified"))
      (node (ref "C22") (pin "1") (pinfunction "1_1") (pintype "unspecified"))
      (node (ref "C28") (pin "1") (pinfunction "1_1") (pintype "unspecified"))
      (node (ref "C30") (pin "2") (pinfunction "2_2") (pintype "unspecified"))
      (node (ref "FPC1") (pin "5") (pinfunction "5_5") (pintype "input"))
      (node (ref "R1") (pin "2") (pinfunction "2_2") (pintype "input"))
      (node (ref "R51") (pin "2") (pinfunction "2_2") (pintype "input"))
      (node (ref "U1") (pin "1") (pinfunction "VDD_1") (pintype "input"))
      (node (ref "U1") (pin "24") (pinfunction "VDD_24") (pintype "input"))
      (node (ref "U1") (pin "48") (pinfunction "VDD_48") (pintype "input"))
      (node (ref "U3") (pin "2") (pinfunction "VOUT_2") (pintype "input"))
      (node (ref "U9") (pin "8") (pinfunction "VCC_8") (pintype "input"))
    )
    (net (code "3") (name "+3.3VA") (class "Default")
      (node (ref "C15") (pin "2") (pinfunction "2_2") (pintype "unspecified"))
      (node (ref "C19") (pin "2") (pinfunction "2_2") (pintype "unspecified"))
      (node (ref "C36") (pin "2") (pinfunction "2_2") (pintype "unspecified"))
      (node (ref "R51") (pin "1") (pinfunction "1_1") (pintype "input"))
      (node (ref "R53") (pin "1") (pinfunction "1_1") (pintype "input"))
      (node (ref "U1") (pin "9") (pinfunction "VDDA_9") (pintype "input"))
      (node (ref "U7") (pin "8") (pinfunction "VCC_8") (pintype "input"))
    )
    (net (code "4") (name "/BT+") (class "Default")
      (node (ref "C26") (pin "2") (pinfunction "2_2") (pintype "unspecified"))
      (node (ref "H5") (pin "1") (pinfunction "1_1") (pintype "unspecified"))
      (node (ref "R50") (pin "2") (pinfunction "2_2") (pintype "input"))
      (node (ref "SW3") (pin "1") (pinfunction "1_1") (pintype "input"))
      (node (ref "U2") (pin "5") (pinfunction "BAT_5") (pintype "input"))
    )
    (net (code "5") (name "/BT-") (class "Default")
      (node (ref "C31") (pin "1") (pinfunction "1_1") (pintype "unspecified"))
      (node (ref "H6") (pin "1") (pinfunction "1_1") (pintype "unspecified"))
      (node (ref "U4") (pin "6") (pinfunction "GND_6") (pintype "input"))
      (node (ref "U5") (pin "2") (pinfunction "S_2") (pintype "input"))
    )
    (net (code "6") (name "/PA0_ADC") (class "Default")
      (node (ref "R70") (pin "2") (pinfunction "2_2") (pintype "unspecified"))
      (node (ref "U1") (pin "10") (pinfunction "PA0_10") (pintype "input"))
      (node (ref "U7") (pin "1") (pinfunction "OUT_1") (pintype "output"))
    )
    (net (code "7") (name "/PA1_ADC1") (class "Default")
      (node (ref "R72") (pin "2") (pinfunction "2_2") (pintype "unspecified"))
      (node (ref "U1") (pin "11") (pinfunction "PA1_11") (pintype "input"))
      (node (ref "U7") (pin "7") (pinfunction "OUT2_7") (pintype "output"))
    )
    (net (code "8") (name "/PA9_GTIM3_CH1") (class "Default")
      (node (ref "R5") (pin "2") (pinfunction "2_2") (pintype "input"))
      (node (ref "U1") (pin "30") (pinfunction "PA9_30") (pintype "input"))
    )
    (net (code "9") (name "/PA13_SWDIO") (class "Default")
      (node (ref "H3") (pin "1") (pinfunction "1_1") (pintype "unspecified"))
      (node (ref "U1") (pin "34") (pinfunction "PA13_34") (pintype "input"))
    )
    (net (code "10") (name "/PA14_SWCLK") (class "Default")
      (node (ref "H1") (pin "1") (pinfunction "1_1") (pintype "unspecified"))
      (node (ref "U1") (pin "37") (pinfunction "PA14_37") (pintype "input"))
    )
    (net (code "11") (name "/PA15_SPI1_CS_LCD_A0") (class "Default")
      (node (ref "FPC1") (pin "8") (pinfunction "8_8") (pintype "input"))
      (node (ref "U1") (pin "38") (pinfunction "PA15_38") (pintype "input"))
    )
    (net (code "12") (name "/PB3_SPI1_SCK") (class "Default")
      (node (ref "FPC1") (pin "7") (pinfunction "7_7") (pintype "input"))
      (node (ref "U1") (pin "39") (pinfunction "PB3_39") (pintype "input"))
    )
    (net (code "13") (name "/PB4_LCD_RST") (class "Default")
      (node (ref "FPC1") (pin "9") (pinfunction "9_9") (pintype "input"))
      (node (ref "U1") (pin "40") (pinfunction "PB4_40") (pintype "input"))
    )
    (net (code "14") (name "/PB5_SPI1_MOSI") (class "Default")
      (node (ref "FPC1") (pin "6") (pinfunction "6_6") (pintype "input"))
      (node (ref "U1") (pin "41") (pinfunction "PB5_41") (pintype "input"))
    )
    (net (code "15") (name "/PB15_GTIM4_CH1_LA_BA") (class "Default")
      (node (ref "U1") (pin "28") (pinfunction "PB15_28") (pintype "input"))
    )
    (net (code "16") (name "GND") (class "Default")
      (node (ref "C1") (pin "1") (pinfunction "1_1") (pintype "unspecified"))
      (node (ref "C11") (pin "2") (pinfunction "2_2") (pintype "unspecified"))
      (node (ref "C12") (pin "1") (pinfunction "1_1") (pintype "input"))
      (node (ref "C13") (pin "1") (pinfunction "1_1") (pintype "unspecified"))
      (node (ref "C15") (pin "1") (pinfunction "1_1") (pintype "unspecified"))
      (node (ref "C16") (pin "1") (pinfunction "1_1") (pintype "input"))
      (node (ref "C19") (pin "1") (pinfunction "1_1") (pintype "unspecified"))
      (node (ref "C22") (pin "2") (pinfunction "2_2") (pintype "unspecified"))
      (node (ref "C23") (pin "2") (pinfunction "2_2") (pintype "unspecified"))
      (node (ref "C24") (pin "1") (pinfunction "1_1") (pintype "unspecified"))
      (node (ref "C26") (pin "1") (pinfunction "1_1") (pintype "unspecified"))
      (node (ref "C28") (pin "2") (pinfunction "2_2") (pintype "unspecified"))
      (node (ref "C29") (pin "1") (pinfunction "1_1") (pintype "unspecified"))
      (node (ref "C30") (pin "1") (pinfunction "1_1") (pintype "unspecified"))
      (node (ref "C33") (pin "2") (pinfunction "2_2") (pintype "unspecified"))
      (node (ref "C35") (pin "1") (pinfunction "1_1") (pintype "unspecified"))
      (node (ref "C45") (pin "1") (pinfunction "1_1") (pintype "input"))
      (node (ref "C46") (pin "1") (pinfunction "1_1") (pintype "input"))
      (node (ref "C47") (pin "1") (pinfunction "1_1") (pintype "input"))
      (node (ref "C48") (pin "1") (pinfunction "1_1") (pintype "input"))
      (node (ref "C49") (pin "2") (pinfunction "2_2") (pintype "unspecified"))
      (node (ref "FPC1") (pin "10") (pinfunction "10_10") (pintype "input"))
      (node (ref "FPC1") (pin "11") (pinfunction "11_11") (pintype "input"))
      (node (ref "FPC1") (pin "12") (pinfunction "12_12") (pintype "input"))
      (node (ref "FPC1") (pin "4") (pinfunction "4_4") (pintype "input"))
      (node (ref "H2") (pin "1") (pinfunction "1_1") (pintype "unspecified"))
      (node (ref "R15") (pin "2") (pinfunction "2_2") (pintype "input"))
      (node (ref "R41") (pin "2") (pinfunction "2_2") (pintype "input"))
      (node (ref "R42") (pin "2") (pinfunction "2_2") (pintype "input"))
      (node (ref "R44") (pin "2") (pinfunction "2_2") (pintype "input"))
      (node (ref "R45") (pin "2") (pinfunction "2_2") (pintype "input"))
      (node (ref "R52") (pin "2") (pinfunction "2_2") (pintype "input"))
      (node (ref "R55") (pin "1") (pinfunction "1_1") (pintype "input"))
      (node (ref "R6") (pin "1") (pinfunction "1_1") (pintype "input"))
      (node (ref "SW1") (pin "1") (pinfunction "1_1") (pintype "input"))
      (node (ref "SW1") (pin "2") (pinfunction "2_2") (pintype "input"))
      (node (ref "SW2") (pin "1") (pinfunction "1_1") (pintype "input"))
      (node (ref "SW2") (pin "2") (pinfunction "2_2") (pintype "input"))
      (node (ref "TP1") (pin "1") (pinfunction "1_1") (pintype "input"))
      (node (ref "TP2") (pin "1") (pinfunction "1_1") (pintype "input"))
      (node (ref "TP3") (pin "1") (pinfunction "1_1") (pintype "input"))
      (node (ref "TP4") (pin "1") (pinfunction "1_1") (pintype "input"))
      (node (ref "U1") (pin "23") (pinfunction "VSS_23") (pintype "input"))
      (node (ref "U1") (pin "47") (pinfunction "VSS_47") (pintype "input"))
      (node (ref "U1") (pin "8") (pinfunction "VSSA_8") (pintype "input"))
      (node (ref "U2") (pin "1") (pinfunction "TEMP_1") (pintype "input"))
      (node (ref "U2") (pin "3") (pinfunction "GND_3") (pintype "input"))
      (node (ref "U3") (pin "1") (pinfunction "VSS_1") (pintype "input"))
      (node (ref "U6") (pin "2") (pinfunction "S_2") (pintype "input"))
      (node (ref "U7") (pin "4") (pinfunction "GND_4") (pintype "input"))
      (node (ref "U9") (pin "4") (pinfunction "GND_4") (pintype "input"))
      (node (ref "USB1") (pin "1") (pinfunction "GND_1") (pintype "input"))
      (node (ref "USB1") (pin "12") (pinfunction "GND_12") (pintype "input"))
      (node (ref "USB1") (pin "13") (pinfunction "SHELL_13") (pintype "input"))
      (node (ref "USB1") (pin "14") (pinfunction "SHELL_14") (pintype "input"))
      (node (ref "X1") (pin "2") (pinfunction "GND_2") (pintype "input"))
      (node (ref "X1") (pin "4") (pinfunction "GND_4") (pintype "input"))
    )
    (net (code "17") (name "Net-(C23-Pad1)") (class "Default")
      (node (ref "C23") (pin "1") (pinfunction "1_1") (pintype "unspecified"))
      (node (ref "R71") (pin "2") (pinfunction "2_2") (pintype "unspecified"))
    )
    (net (code "18") (name "Net-(C32-Pad1)") (class "Default")
      (node (ref "C32") (pin "1") (pinfunction "1_1") (pintype "unspecified"))
      (node (ref "FPC1") (pin "3") (pinfunction "3_3") (pintype "input"))
    )
    (net (code "19") (name "Net-(C32-Pad2)") (class "Default")
      (node (ref "C32") (pin "2") (pinfunction "2_2") (pintype "unspecified"))
      (node (ref "FPC1") (pin "2") (pinfunction "2_2") (pintype "input"))
    )
    (net (code "20") (name "Net-(C33-Pad1)") (class "Default")
      (node (ref "C33") (pin "1") (pinfunction "1_1") (pintype "unspecified"))
      (node (ref "FPC1") (pin "1") (pinfunction "1_1") (pintype "input"))
    )
    (net (code "21") (name "Net-(C40-Pad1)") (class "Default")
      (node (ref "C40") (pin "1") (pinfunction "1_1") (pintype "input"))
      (node (ref "C41") (pin "2") (pinfunction "2_2") (pintype "input"))
      (node (ref "C42") (pin "2") (pinfunction "2_2") (pintype "input"))
      (node (ref "C43") (pin "2") (pinfunction "2_2") (pintype "input"))
      (node (ref "C44") (pin "2") (pinfunction "2_2") (pintype "input"))
      (node (ref "H7") (pin "1") (pinfunction "1_1") (pintype "input"))
      (node (ref "L1") (pin "2") (pinfunction "2_2") (pintype "input"))
    )
    (net (code "22") (name "Net-(C45-Pad2)") (class "Default")
      (node (ref "C45") (pin "2") (pinfunction "2_2") (pintype "input"))
      (node (ref "C6") (pin "2") (pinfunction "2_2") (pintype "input"))
      (node (ref "R2") (pin "1") (pinfunction "1_1") (pintype "input"))
    )
    (net (code "23") (name "Net-(C46-Pad2)") (class "Default")
      (node (ref "C46") (pin "2") (pinfunction "2_2") (pintype "input"))
      (node (ref "R2") (pin "2") (pinfunction "2_2") (pintype "input"))
      (node (ref "R3") (pin "1") (pinfunction "1_1") (pintype "input"))
    )
    (net (code "24") (name "Net-(C47-Pad2)") (class "Default")
      (node (ref "C47") (pin "2") (pinfunction "2_2") (pintype "input"))
      (node (ref "R3") (pin "2") (pinfunction "2_2") (pintype "input"))
      (node (ref "R4") (pin "1") (pinfunction "1_1") (pintype "input"))
    )
    (net (code "25") (name "Net-(C48-Pad2)") (class "Default")
      (node (ref "C48") (pin "2") (pinfunction "2_2") (pintype "input"))
      (node (ref "R4") (pin "2") (pinfunction "2_2") (pintype "input"))
      (node (ref "R5") (pin "1") (pinfunction "1_1") (pintype "input"))
    )
    (net (code "26") (name "Net-(C49-Pad1)") (class "Default")
      (node (ref "C49") (pin "1") (pinfunction "1_1") (pintype "unspecified"))
      (node (ref "R69") (pin "2") (pinfunction "2_2") (pintype "unspecified"))
    )
    (net (code "27") (name "Net-(H7-Pad2)") (class "Default")
      (node (ref "H7") (pin "2") (pinfunction "2_2") (pintype "input"))
      (node (ref "L3") (pin "1") (pinfunction "1_1") (pintype "input"))
      (node (ref "R60") (pin "2") (pinfunction "2_2") (pintype "unspecified"))
      (node (ref "R67") (pin "1") (pinfunction "1_1") (pintype "unspecified"))
      (node (ref "R68") (pin "1") (pinfunction "1_1") (pintype "unspecified"))
    )
    (net (code "28") (name "Net-(H7-Pad3)") (class "Default")
      (node (ref "H7") (pin "3") (pinfunction "3_3") (pintype "input"))
      (node (ref "L3") (pin "2") (pinfunction "2_2") (pintype "input"))
      (node (ref "R16") (pin "1") (pinfunction "1_1") (pintype "unspecified"))
      (node (ref "R17") (pin "1") (pinfunction "1_1") (pintype "unspecified"))
      (node (ref "R59") (pin "1") (pinfunction "1_1") (pintype "unspecified"))
    )
    (net (code "29") (name "Net-(H7-Pad5)") (class "Default")
      (node (ref "H7") (pin "5") (pinfunction "5_5") (pintype "input"))
      (node (ref "L2") (pin "2") (pinfunction "2_2") (pintype "input"))
      (node (ref "R61") (pin "1") (pinfunction "1_1") (pintype "unspecified"))
      (node (ref "R62") (pin "1") (pinfunction "1_1") (pintype "unspecified"))
      (node (ref "R66") (pin "2") (pinfunction "2_2") (pintype "unspecified"))
    )
    (net (code "30") (name "Net-(H7-Pad6)") (class "Default")
      (node (ref "H7") (pin "6") (pinfunction "6_6") (pintype "input"))
      (node (ref "L2") (pin "1") (pinfunction "1_1") (pintype "input"))
      (node (ref "R63") (pin "1") (pinfunction "1_1") (pintype "unspecified"))
      (node (ref "R64") (pin "1") (pinfunction "1_1") (pintype "unspecified"))
      (node (ref "R65") (pin "1") (pinfunction "1_1") (pintype "unspecified"))
    )
    (net (code "31") (name "Net-(LED11-A)") (class "Default")
      (node (ref "C24") (pin "2") (pinfunction "2_2") (pintype "unspecified"))
      (node (ref "LED11") (pin "1") (pinfunction "A_1") (pintype "input"))
      (node (ref "LED12") (pin "1") (pinfunction "A_1") (pintype "input"))
      (node (ref "U2") (pin "4") (pinfunction "Vcc_4") (pintype "input"))
      (node (ref "U2") (pin "8") (pinfunction "CE_8") (pintype "input"))
      (node (ref "USB1") (pin "11") (pinfunction "VBUS_11") (pintype "input"))
      (node (ref "USB1") (pin "2") (pinfunction "VBUS_2") (pintype "input"))
    )
    (net (code "32") (name "Net-(LED11-K)") (class "Default")
      (node (ref "LED11") (pin "2") (pinfunction "K_2") (pintype "input"))
      (node (ref "R38") (pin "2") (pinfunction "2_2") (pintype "input"))
    )
    (net (code "33") (name "Net-(LED12-K)") (class "Default")
      (node (ref "LED12") (pin "2") (pinfunction "K_2") (pintype "input"))
      (node (ref "R39") (pin "2") (pinfunction "2_2") (pintype "input"))
    )
    (net (code "34") (name "Net-(R13-Pad1)") (class "Default")
      (node (ref "R13") (pin "1") (pinfunction "1_1") (pintype "input"))
      (node (ref "SW1") (pin "3") (pinfunction "3_3") (pintype "input"))
      (node (ref "SW1") (pin "4") (pinfunction "4_4") (pintype "input"))
    )
    (net (code "35") (name "Net-(R14-Pad1)") (class "Default")
      (node (ref "R14") (pin "1") (pinfunction "1_1") (pintype "input"))
      (node (ref "SW2") (pin "3") (pinfunction "3_3") (pintype "input"))
      (node (ref "SW2") (pin "4") (pinfunction "4_4") (pintype "input"))
    )
    (net (code "36") (name "Net-(R42-Pad1)") (class "Default")
      (node (ref "R42") (pin "1") (pinfunction "1_1") (pintype "input"))
      (node (ref "R43") (pin "2") (pinfunction "2_2") (pintype "input"))
      (node (ref "R45") (pin "1") (pinfunction "1_1") (pintype "input"))
    )
    (net (code "37") (name "Net-(U1-BOOT0)") (class "Default")
      (node (ref "R15") (pin "1") (pinfunction "1_1") (pintype "input"))
      (node (ref "U1") (pin "44") (pinfunction "BOOT0_44") (pintype "input"))
    )
    (net (code "38") (name "Net-(U1-PB6)") (class "Default")
      (node (ref "R14") (pin "2") (pinfunction "2_2") (pintype "input"))
      (node (ref "U1") (pin "42") (pinfunction "PB6_42") (pintype "input"))
    )
    (net (code "39") (name "Net-(U1-PB7)") (class "Default")
      (node (ref "R13") (pin "2") (pinfunction "2_2") (pintype "input"))
      (node (ref "U1") (pin "43") (pinfunction "PB7_43") (pintype "input"))
    )
    (net (code "40") (name "Net-(U1-PF0-OSC_IN)") (class "Default")
      (node (ref "C12") (pin "2") (pinfunction "2_2") (pintype "input"))
      (node (ref "U1") (pin "5") (pinfunction "PF0-OSC_IN_5") (pintype "input"))
      (node (ref "X1") (pin "3") (pinfunction "3_3") (pintype "input"))
    )
    (net (code "41") (name "Net-(U1-PF1-OSC_OUT)") (class "Default")
      (node (ref "C16") (pin "2") (pinfunction "2_2") (pintype "input"))
      (node (ref "U1") (pin "6") (pinfunction "PF1-OSC_OUT_6") (pintype "input"))
      (node (ref "X1") (pin "1") (pinfunction "1_1") (pintype "input"))
    )
    (net (code "42") (name "Net-(U2-CHRG#)") (class "Default")
      (node (ref "R38") (pin "1") (pinfunction "1_1") (pintype "input"))
      (node (ref "U2") (pin "7") (pinfunction "CHRG#_7") (pintype "input"))
    )
    (net (code "43") (name "Net-(U2-PROG)") (class "Default")
      (node (ref "R43") (pin "1") (pinfunction "1_1") (pintype "input"))
      (node (ref "U2") (pin "2") (pinfunction "PROG_2") (pintype "input"))
    )
    (net (code "44") (name "Net-(U2-STDBY#)") (class "Default")
      (node (ref "R39") (pin "1") (pinfunction "1_1") (pintype "input"))
      (node (ref "U2") (pin "6") (pinfunction "STDBY#_6") (pintype "input"))
    )
    (net (code "45") (name "Net-(U4-CS)") (class "Default")
      (node (ref "R55") (pin "2") (pinfunction "2_2") (pintype "input"))
      (node (ref "U4") (pin "2") (pinfunction "CS_2") (pintype "input"))
    )
    (net (code "46") (name "Net-(U4-OC)") (class "Default")
      (node (ref "U4") (pin "3") (pinfunction "OC_3") (pintype "input"))
      (node (ref "U6") (pin "1") (pinfunction "G_1") (pintype "input"))
    )
    (net (code "47") (name "Net-(U4-OD)") (class "Default")
      (node (ref "U4") (pin "1") (pinfunction "OD_1") (pintype "input"))
      (node (ref "U5") (pin "1") (pinfunction "G_1") (pintype "input"))
    )
    (net (code "48") (name "Net-(U4-VCC)") (class "Default")
      (node (ref "C31") (pin "2") (pinfunction "2_2") (pintype "unspecified"))
      (node (ref "R50") (pin "1") (pinfunction "1_1") (pintype "input"))
      (node (ref "U4") (pin "5") (pinfunction "VCC_5") (pintype "input"))
    )
    (net (code "49") (name "Net-(U5-D)") (class "Default")
      (node (ref "U5") (pin "3") (pinfunction "D_3") (pintype "input"))
      (node (ref "U6") (pin "3") (pinfunction "D_3") (pintype "input"))
    )
    (net (code "50") (name "Net-(U7A-IN1+)") (class "Default")
      (node (ref "R16") (pin "2") (pinfunction "2_2") (pintype "unspecified"))
      (node (ref "R17") (pin "2") (pinfunction "2_2") (pintype "unspecified"))
      (node (ref "R69") (pin "1") (pinfunction "1_1") (pintype "unspecified"))
      (node (ref "U7") (pin "3") (pinfunction "IN1+_3") (pintype "input"))
    )
    (net (code "51") (name "Net-(U7A-IN1-)") (class "Default")
      (node (ref "R67") (pin "2") (pinfunction "2_2") (pintype "unspecified"))
      (node (ref "R68") (pin "2") (pinfunction "2_2") (pintype "unspecified"))
      (node (ref "R70") (pin "1") (pinfunction "1_1") (pintype "unspecified"))
      (node (ref "U7") (pin "2") (pinfunction "IN1-_2") (pintype "input"))
    )
    (net (code "52") (name "Net-(U7B-IN2+)") (class "Default")
      (node (ref "R63") (pin "2") (pinfunction "2_2") (pintype "unspecified"))
      (node (ref "R64") (pin "2") (pinfunction "2_2") (pintype "unspecified"))
      (node (ref "R71") (pin "1") (pinfunction "1_1") (pintype "unspecified"))
      (node (ref "U7") (pin "5") (pinfunction "IN2+_5") (pintype "input"))
    )
    (net (code "53") (name "Net-(U7B-IN2-)") (class "Default")
      (node (ref "R61") (pin "2") (pinfunction "2_2") (pintype "unspecified"))
      (node (ref "R62") (pin "2") (pinfunction "2_2") (pintype "unspecified"))
      (node (ref "R72") (pin "1") (pinfunction "1_1") (pintype "unspecified"))
      (node (ref "U7") (pin "6") (pinfunction "IN2-_6") (pintype "input"))
    )
    (net (code "54") (name "Net-(U9A-IN1+)") (class "Default")
      (node (ref "C6") (pin "1") (pinfunction "1_1") (pintype "input"))
      (node (ref "R1") (pin "1") (pinfunction "1_1") (pintype "input"))
      (node (ref "R6") (pin "2") (pinfunction "2_2") (pintype "input"))
      (node (ref "U9") (pin "3") (pinfunction "IN1+_3") (pintype "input"))
    )
    (net (code "55") (name "Net-(U9A-IN1-)") (class "Default")
      (node (ref "R10") (pin "2") (pinfunction "2_2") (pintype "input"))
      (node (ref "R56") (pin "1") (pinfunction "1_1") (pintype "unspecified"))
      (node (ref "R57") (pin "1") (pinfunction "1_1") (pintype "unspecified"))
      (node (ref "R58") (pin "1") (pinfunction "1_1") (pintype "unspecified"))
      (node (ref "R7") (pin "2") (pinfunction "2_2") (pintype "unspecified"))
      (node (ref "U9") (pin "2") (pinfunction "IN1-_2") (pintype "input"))
    )
    (net (code "56") (name "Net-(U9A-OUT)") (class "Default")
      (node (ref "C40") (pin "2") (pinfunction "2_2") (pintype "input"))
      (node (ref "R7") (pin "1") (pinfunction "1_1") (pintype "unspecified"))
      (node (ref "R9") (pin "1") (pinfunction "1_1") (pintype "unspecified"))
      (node (ref "U9") (pin "1") (pinfunction "OUT_1") (pintype "output"))
    )
    (net (code "57") (name "Net-(U9B-IN2+)") (class "Default")
      (node (ref "C11") (pin "1") (pinfunction "1_1") (pintype "unspecified"))
      (node (ref "R10") (pin "1") (pinfunction "1_1") (pintype "input"))
      (node (ref "R56") (pin "2") (pinfunction "2_2") (pintype "unspecified"))
      (node (ref "R57") (pin "2") (pinfunction "2_2") (pintype "unspecified"))
      (node (ref "R58") (pin "2") (pinfunction "2_2") (pintype "unspecified"))
      (node (ref "U9") (pin "5") (pinfunction "IN2+_5") (pintype "input"))
    )
    (net (code "58") (name "Net-(U9B-IN2-)") (class "Default")
      (node (ref "R12") (pin "1") (pinfunction "1_1") (pintype "unspecified"))
      (node (ref "R9") (pin "2") (pinfunction "2_2") (pintype "unspecified"))
      (node (ref "U9") (pin "6") (pinfunction "IN2-_6") (pintype "input"))
    )
    (net (code "59") (name "Net-(U9B-OUT2)") (class "Default")
      (node (ref "C41") (pin "1") (pinfunction "1_1") (pintype "input"))
      (node (ref "C42") (pin "1") (pinfunction "1_1") (pintype "input"))
      (node (ref "C43") (pin "1") (pinfunction "1_1") (pintype "input"))
      (node (ref "C44") (pin "1") (pinfunction "1_1") (pintype "input"))
      (node (ref "H7") (pin "4") (pinfunction "4_4") (pintype "input"))
      (node (ref "L1") (pin "1") (pinfunction "1_1") (pintype "input"))
      (node (ref "R12") (pin "2") (pinfunction "2_2") (pintype "unspecified"))
      (node (ref "U9") (pin "7") (pinfunction "OUT2_7") (pintype "output"))
    )
    (net (code "60") (name "Net-(USB1-CC1)") (class "Default")
      (node (ref "R44") (pin "1") (pinfunction "1_1") (pintype "input"))
      (node (ref "USB1") (pin "4") (pinfunction "CC1_4") (pintype "input"))
    )
    (net (code "61") (name "Net-(USB1-CC2)") (class "Default")
      (node (ref "R41") (pin "1") (pinfunction "1_1") (pintype "input"))
      (node (ref "USB1") (pin "10") (pinfunction "CC2_10") (pintype "input"))
    )
    (net (code "62") (name "VCC") (class "Default")
      (node (ref "C29") (pin "2") (pinfunction "2_2") (pintype "unspecified"))
      (node (ref "SW3") (pin "2") (pinfunction "2_2") (pintype "input"))
      (node (ref "SW3") (pin "3") (pinfunction "3_3") (pintype "input"))
      (node (ref "U3") (pin "3") (pinfunction "VIN_3") (pintype "input"))
    )
    (net (code "63") (name "unconnected-(U1-NRST-Pad7)") (class "Default")
      (node (ref "U1") (pin "7") (pinfunction "NRST_7") (pintype "input"))
    )
    (net (code "64") (name "unconnected-(U1-PA2-Pad12)") (class "Default")
      (node (ref "U1") (pin "12") (pinfunction "PA2_12") (pintype "input"))
    )
    (net (code "65") (name "unconnected-(U1-PA3-Pad13)") (class "Default")
      (node (ref "U1") (pin "13") (pinfunction "PA3_13") (pintype "input"))
    )
    (net (code "66") (name "unconnected-(U1-PA4-Pad14)") (class "Default")
      (node (ref "U1") (pin "14") (pinfunction "PA4_14") (pintype "input"))
    )
    (net (code "67") (name "unconnected-(U1-PA5-Pad15)") (class "Default")
      (node (ref "U1") (pin "15") (pinfunction "PA5_15") (pintype "input"))
    )
    (net (code "68") (name "unconnected-(U1-PA6-Pad16)") (class "Default")
      (node (ref "U1") (pin "16") (pinfunction "PA6_16") (pintype "input"))
    )
    (net (code "69") (name "unconnected-(U1-PA7-Pad17)") (class "Default")
      (node (ref "U1") (pin "17") (pinfunction "PA7_17") (pintype "input"))
    )
    (net (code "70") (name "unconnected-(U1-PA8-Pad29)") (class "Default")
      (node (ref "U1") (pin "29") (pinfunction "PA8_29") (pintype "input"))
    )
    (net (code "71") (name "unconnected-(U1-PA10-Pad31)") (class "Default")
      (node (ref "U1") (pin "31") (pinfunction "PA10_31") (pintype "input"))
    )
    (net (code "72") (name "unconnected-(U1-PA11-Pad32)") (class "Default")
      (node (ref "U1") (pin "32") (pinfunction "PA11_32") (pintype "input"))
    )
    (net (code "73") (name "unconnected-(U1-PA12-Pad33)") (class "Default")
      (node (ref "U1") (pin "33") (pinfunction "PA12_33") (pintype "input"))
    )
    (net (code "74") (name "unconnected-(U1-PB0-Pad18)") (class "Default")
      (node (ref "U1") (pin "18") (pinfunction "PB0_18") (pintype "input"))
    )
    (net (code "75") (name "unconnected-(U1-PB1-Pad19)") (class "Default")
      (node (ref "U1") (pin "19") (pinfunction "PB1_19") (pintype "input"))
    )
    (net (code "76") (name "unconnected-(U1-PB2-Pad20)") (class "Default")
      (node (ref "U1") (pin "20") (pinfunction "PB2_20") (pintype "input"))
    )
    (net (code "77") (name "unconnected-(U1-PB8-Pad45)") (class "Default")
      (node (ref "U1") (pin "45") (pinfunction "PB8_45") (pintype "input"))
    )
    (net (code "78") (name "unconnected-(U1-PB9-Pad46)") (class "Default")
      (node (ref "U1") (pin "46") (pinfunction "PB9_46") (pintype "input"))
    )
    (net (code "79") (name "unconnected-(U1-PB10-Pad21)") (class "Default")
      (node (ref "U1") (pin "21") (pinfunction "PB10_21") (pintype "input"))
    )
    (net (code "80") (name "unconnected-(U1-PB11-Pad22)") (class "Default")
      (node (ref "U1") (pin "22") (pinfunction "PB11_22") (pintype "input"))
    )
    (net (code "81") (name "unconnected-(U1-PB12-Pad25)") (class "Default")
      (node (ref "U1") (pin "25") (pinfunction "PB12_25") (pintype "input"))
    )
    (net (code "82") (name "unconnected-(U1-PB13-Pad26)") (class "Default")
      (node (ref "U1") (pin "26") (pinfunction "PB13_26") (pintype "input"))
    )
    (net (code "83") (name "unconnected-(U1-PB14-Pad27)") (class "Default")
      (node (ref "U1") (pin "27") (pinfunction "PB14_27") (pintype "input"))
    )
    (net (code "84") (name "unconnected-(U1-PC13-Pad2)") (class "Default")
      (node (ref "U1") (pin "2") (pinfunction "PC13_2") (pintype "input"))
    )
    (net (code "85") (name "unconnected-(U1-PC14-OSC32_IN-Pad3)") (class "Default")
      (node (ref "U1") (pin "3") (pinfunction "PC14-OSC32_IN_3") (pintype "input"))
    )
    (net (code "86") (name "unconnected-(U1-PC15-OSC32_OUT-Pad4)") (class "Default")
      (node (ref "U1") (pin "4") (pinfunction "PC15-OSC32_OUT_4") (pintype "input"))
    )
    (net (code "87") (name "unconnected-(U1-PF6-Pad35)") (class "Default")
      (node (ref "U1") (pin "35") (pinfunction "PF6_35") (pintype "input"))
    )
    (net (code "88") (name "unconnected-(U1-PF7-Pad36)") (class "Default")
      (node (ref "U1") (pin "36") (pinfunction "PF7_36") (pintype "input"))
    )
    (net (code "89") (name "unconnected-(U4-TD-Pad4)") (class "Default")
      (node (ref "U4") (pin "4") (pinfunction "TD_4") (pintype "input"))
    )
    (net (code "90") (name "unconnected-(USB1-DN1-Pad7)") (class "Default")
      (node (ref "USB1") (pin "7") (pinfunction "DN1_7") (pintype "input"))
    )
    (net (code "91") (name "unconnected-(USB1-DN2-Pad5)") (class "Default")
      (node (ref "USB1") (pin "5") (pinfunction "DN2_5") (pintype "input"))
    )
    (net (code "92") (name "unconnected-(USB1-DP1-Pad6)") (class "Default")
      (node (ref "USB1") (pin "6") (pinfunction "DP1_6") (pintype "input"))
    )
    (net (code "93") (name "unconnected-(USB1-DP2-Pad8)") (class "Default")
      (node (ref "USB1") (pin "8") (pinfunction "DP2_8") (pintype "input"))
    )
    (net (code "94") (name "unconnected-(USB1-SBU1-Pad9)") (class "Default")
      (node (ref "USB1") (pin "9") (pinfunction "SBU1_9") (pintype "input"))
    )
    (net (code "95") (name "unconnected-(USB1-SBU2-Pad3)") (class "Default")
      (node (ref "USB1") (pin "3") (pinfunction "SBU2_3") (pintype "input"))
    )
  )
)
